# S01.net
KiCad netlist of a schematic drawn in Altium Designer
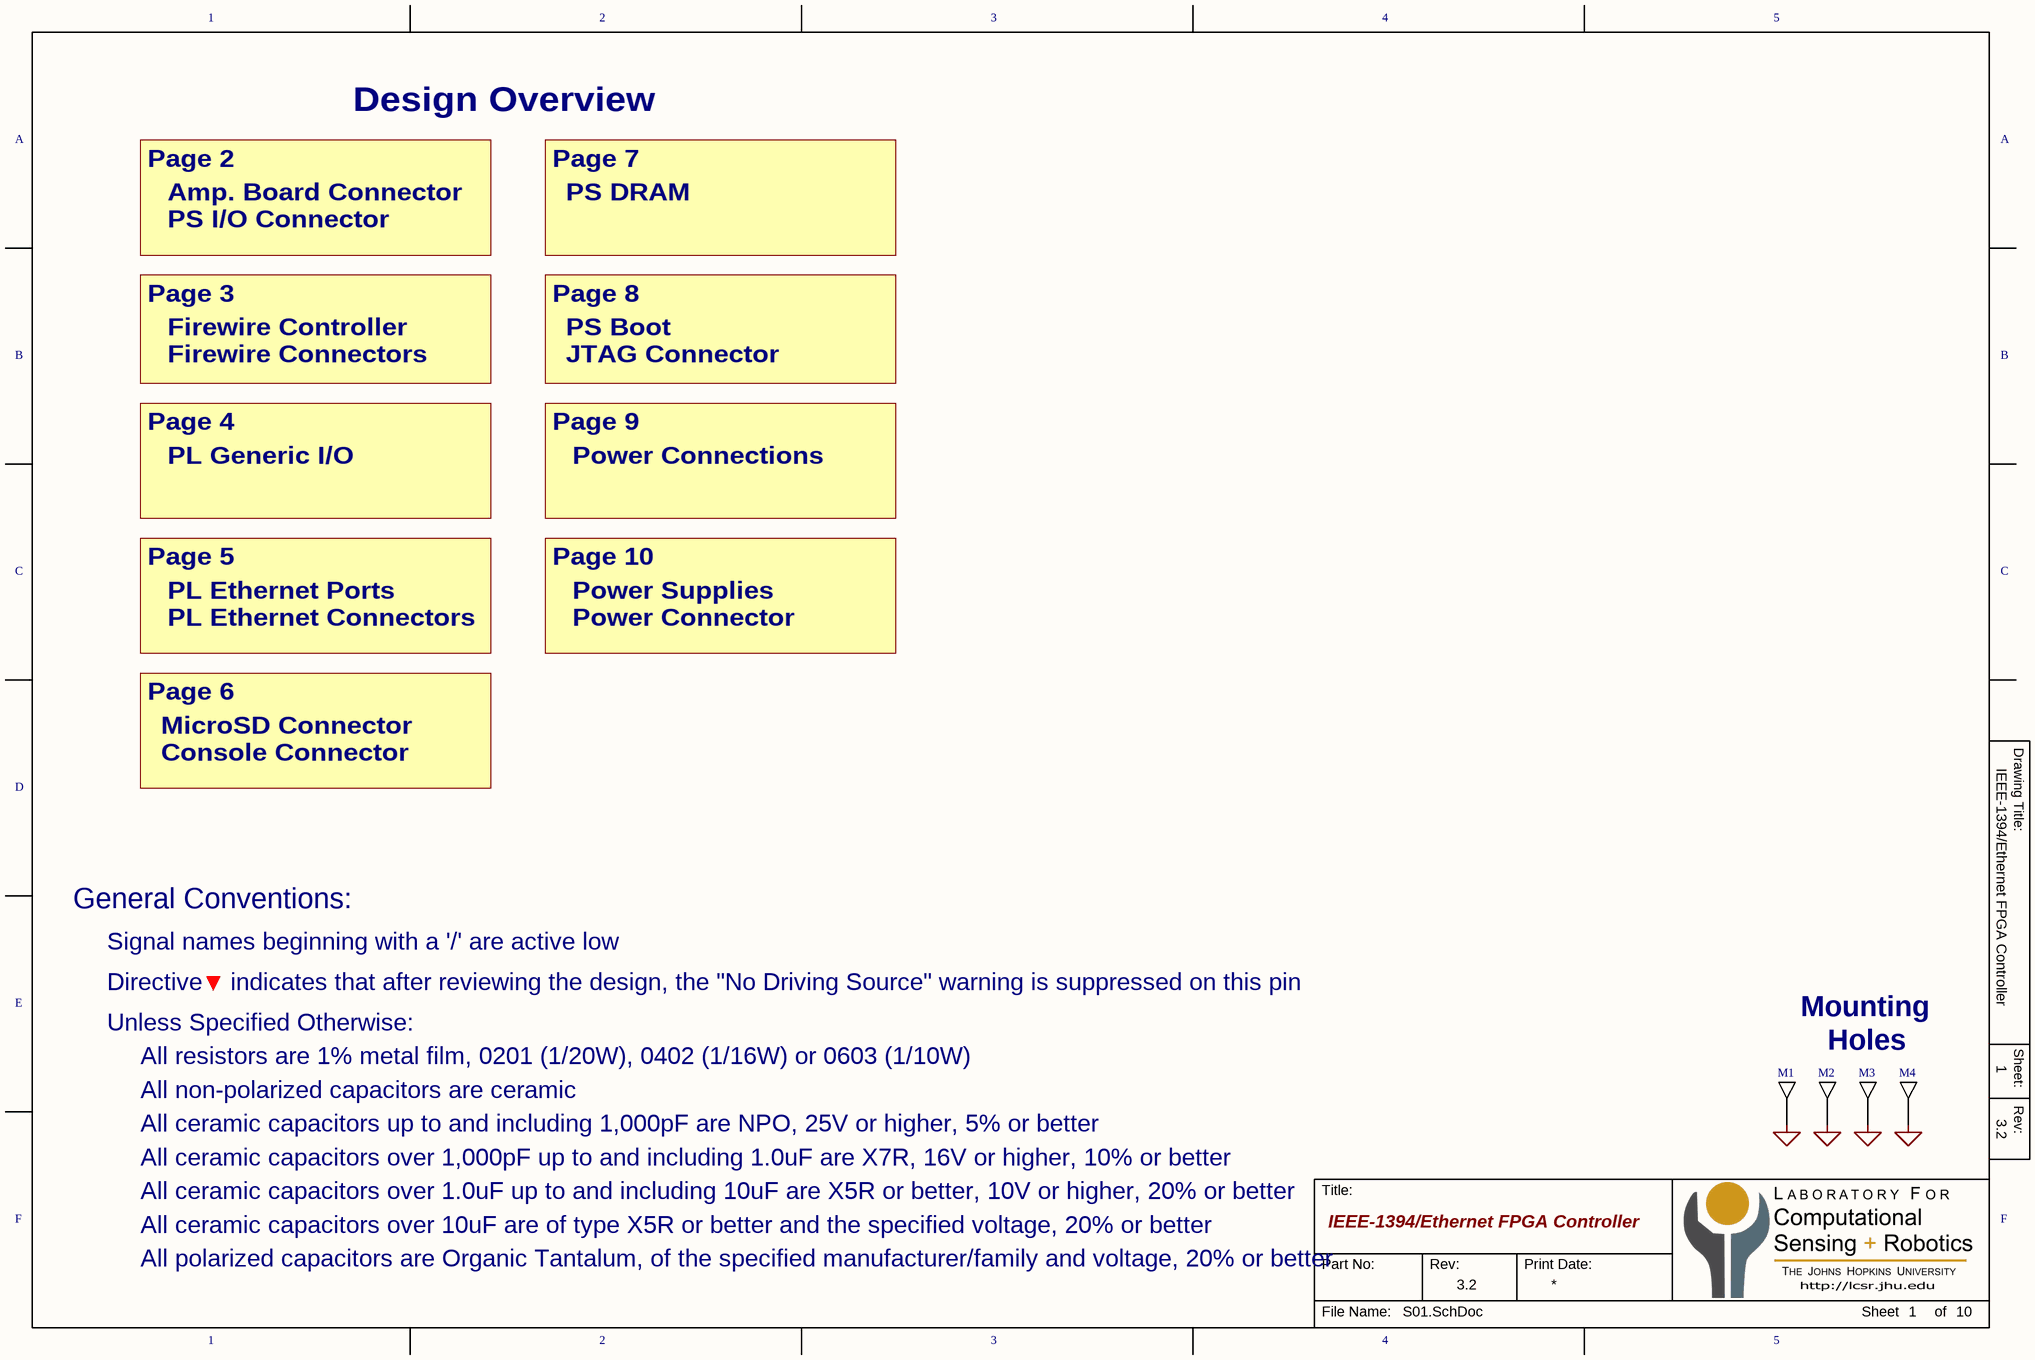
[diagram p0: S01.SchDoc]

(export (version "E")
  (design (tool "Eeschema 10.0.6"))
  (components
    (comp (ref "M1")
      (value "MHOLE")
      (footprint "MHOLE4")
      (description "Mounting Hole")
      (libsource (lib "LibJHU") (part "MHOLE"))
    )
    (comp (ref "M2")
      (value "MHOLE")
      (footprint "MHOLE4")
      (description "Mounting Hole")
      (libsource (lib "LibJHU") (part "MHOLE"))
    )
    (comp (ref "M3")
      (value "MHOLE")
      (footprint "MHOLE4")
      (description "Mounting Hole")
      (libsource (lib "LibJHU") (part "MHOLE"))
    )
    (comp (ref "M4")
      (value "MHOLE")
      (footprint "MHOLE4")
      (description "Mounting Hole")
      (libsource (lib "LibJHU") (part "MHOLE"))
    )
  )
  (nets
    (net (code "1") (name "GND") (class "Default")
      (node (ref "M1") (pin "1") (pinfunction "1_1") (pintype "passive"))
      (node (ref "M2") (pin "1") (pinfunction "1_1") (pintype "passive"))
      (node (ref "M3") (pin "1") (pinfunction "1_1") (pintype "passive"))
      (node (ref "M4") (pin "1") (pinfunction "1_1") (pintype "passive"))
    )
  )
)
